# LedDriver7W.net
KiCad netlist of a schematic drawn in Altium Designer
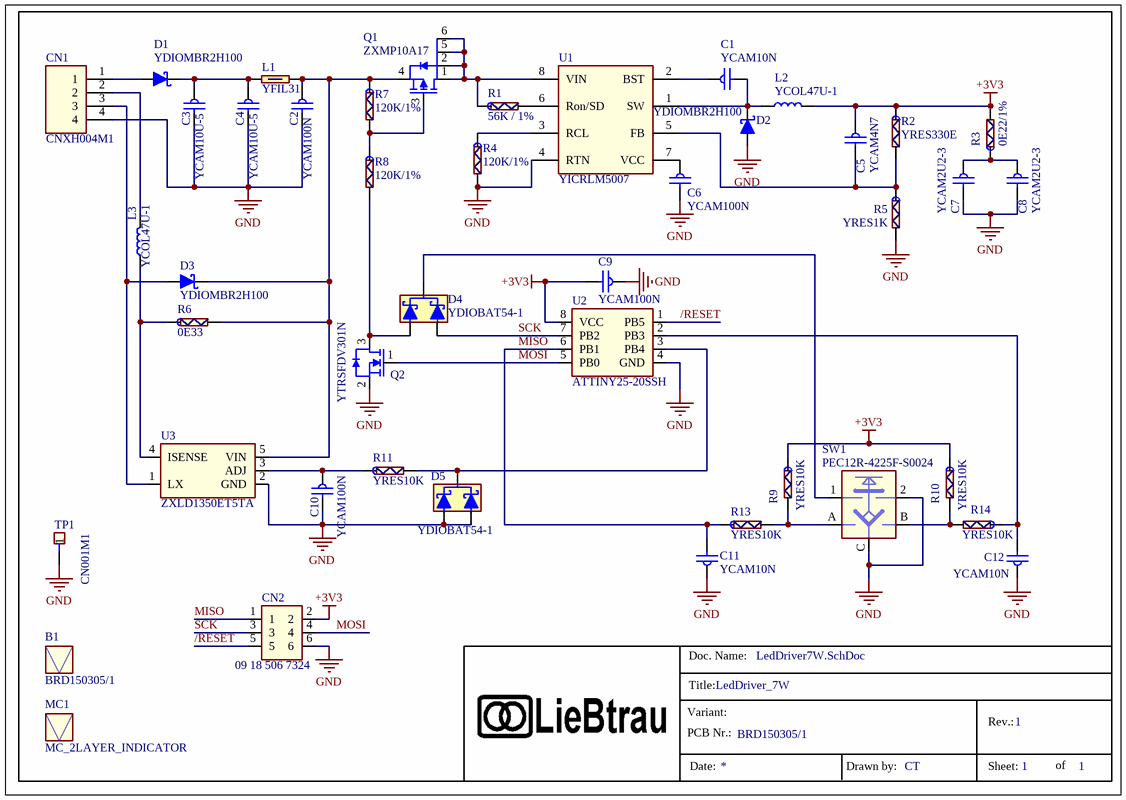
[diagram p0: LedDriver7W.SchDoc]

(export (version "E")
  (design (tool "Eeschema 10.0.6"))
  (components
    (comp (ref "B1") (value "~") (footprint "MC_BoardNr") (libsource (lib "Testing") (part "BD_PCB")))
    (comp (ref "C1")
      (value "YCAM10N")
      (footprint "CA_STD1206_H16")
      (description "10N")
      (libsource (lib "Testing") (part "CA_STD_NonPolar"))
    )
    (comp (ref "C2")
      (value "YCAM100N")
      (footprint "CA_STD1206_H16")
      (description "100N")
      (libsource (lib "Testing") (part "CA_STD_NonPolar"))
    )
    (comp (ref "C3")
      (value "YCAM10U-5")
      (footprint "CA_STD1206_H16")
      (description "10U")
      (libsource (lib "Testing") (part "CA_STD_NonPolar"))
    )
    (comp (ref "C4")
      (value "YCAM10U-5")
      (footprint "CA_STD1206_H16")
      (description "10U")
      (libsource (lib "Testing") (part "CA_STD_NonPolar"))
    )
    (comp (ref "C5")
      (value "YCAM4N7")
      (footprint "CA_STD1206_H16")
      (description "4N7")
      (libsource (lib "Testing") (part "CA_STD_NonPolar"))
    )
    (comp (ref "C6")
      (value "YCAM100N")
      (footprint "CA_STD1206_H16")
      (description "100N")
      (libsource (lib "Testing") (part "CA_STD_NonPolar"))
    )
    (comp (ref "C7")
      (value "YCAM2U2-3")
      (footprint "CA_STD1206_H16")
      (description "2U2")
      (libsource (lib "Testing") (part "CA_STD_NonPolar"))
    )
    (comp (ref "C8")
      (value "YCAM2U2-3")
      (footprint "CA_STD1206_H16")
      (description "2U2")
      (libsource (lib "Testing") (part "CA_STD_NonPolar"))
    )
    (comp (ref "C9")
      (value "YCAM100N")
      (footprint "CA_STD1206_H16")
      (description "100N")
      (libsource (lib "") (part "CA_STD_NonPolar_1"))
    )
    (comp (ref "C10")
      (value "YCAM100N")
      (footprint "CA_STD1206_H16")
      (description "100N")
      (libsource (lib "Testing") (part "CA_STD_NonPolar"))
    )
    (comp (ref "C11")
      (value "YCAM10N")
      (footprint "CA_STD1206_H16")
      (description "10N")
      (libsource (lib "Testing") (part "CA_STD_NonPolar"))
    )
    (comp (ref "C12")
      (value "YCAM10N")
      (footprint "CA_STD1206_H16")
      (description "10N")
      (libsource (lib "Testing") (part "CA_STD_NonPolar"))
    )
    (comp (ref "CN1")
      (value "CNXH004M1")
      (footprint "CN_JST-B4B-XH")
      (description "HEADER, VERT, 1x4WAY")
      (libsource (lib "Testing") (part "CN_4P"))
    )
    (comp (ref "CN2")
      (value "09 18 506 7324")
      (footprint "CN_HDR2x3_SHROUDED")
      (description "HEADER, VERT, N/LATCH, 2x3WAY")
      (libsource (lib "Testing") (part "CN_2x3P"))
    )
    (comp (ref "D1")
      (value "YDIOMBR2H100")
      (footprint "DI_SMB")
      (description "MBRS2H100")
      (libsource (lib "Testing") (part "DI_STD_Schottky"))
    )
    (comp (ref "D2")
      (value "YDIOMBR2H100")
      (footprint "DI_SMB")
      (description "MBRS2H100")
      (libsource (lib "Testing") (part "DI_STD_Schottky"))
    )
    (comp (ref "D3")
      (value "YDIOMBR2H100")
      (footprint "DI_SMB")
      (description "MBRS2H100")
      (libsource (lib "Testing") (part "DI_STD_Schottky"))
    )
    (comp (ref "D4")
      (value "YDIOBAT54-1")
      (footprint "SC_SOT23_3P")
      (description "BAT54C")
      (libsource (lib "Testing") (part "DI_BAT54C"))
    )
    (comp (ref "D5")
      (value "YDIOBAT54-1")
      (footprint "SC_SOT23_3P")
      (description "BAT54C")
      (libsource (lib "") (part "DI_BAT54C_1"))
    )
    (comp (ref "L1")
      (value "YFIL31")
      (footprint "CL_STD1206_H16")
      (description "600E")
      (libsource (lib "Testing") (part "CL_STD_FerriteBead"))
    )
    (comp (ref "L2")
      (value "YCOL47U-1")
      (footprint "CL_STD6045")
      (description "47UH")
      (libsource (lib "Testing") (part "CL_STD_Inductor"))
    )
    (comp (ref "L3")
      (value "YCOL47U-1")
      (footprint "CL_STD6045")
      (description "47UH")
      (libsource (lib "Testing") (part "CL_STD_Inductor"))
    )
    (comp (ref "MC1")
      (value "MC_2LAYER_INDICATOR")
      (footprint "MC_2LAYER_INDICATOR")
      (libsource (lib "Testing") (part "MC_MechPart_No_BOM"))
    )
    (comp (ref "Q1")
      (value "ZXMP10A17")
      (footprint "SC_SOT23_6P")
      (libsource (lib "Diverse") (part "TR_FETP_ZXMP10A17"))
    )
    (comp (ref "Q2")
      (value "YTRSFDV301N")
      (footprint "SC_SOT23_3P")
      (description "FDV301N")
      (libsource (lib "Testing") (part "TR_FETN_ENH-FDV301N"))
    )
    (comp (ref "R1")
      (value "56K / 1%")
      (footprint "RE_STD1206_H6")
      (description "56K")
      (libsource (lib "") (part "RE_STD_Resistor_3"))
    )
    (comp (ref "R2")
      (value "YRES330E")
      (footprint "RE_STD1206_H6")
      (description "330E")
      (libsource (lib "Testing") (part "RE_STD_Resistor"))
    )
    (comp (ref "R3")
      (value "0E22/1%")
      (footprint "RE_STD1206_H6")
      (description "0E22")
      (libsource (lib "") (part "RE_STD_Resistor_1"))
    )
    (comp (ref "R4")
      (value "120K/1%")
      (footprint "RE_STD1206_H6")
      (description "120K")
      (libsource (lib "Testing") (part "RE_STD_Resistor"))
    )
    (comp (ref "R5")
      (value "YRES1K")
      (footprint "RE_STD1206_H6")
      (description "1K")
      (libsource (lib "Testing") (part "RE_STD_Resistor"))
    )
    (comp (ref "R6")
      (value "0E33")
      (footprint "RE_STD1206_H6")
      (libsource (lib "") (part "RE_STD_Resistor_3"))
    )
    (comp (ref "R7")
      (value "120K/1%")
      (footprint "RE_STD1206_H6")
      (description "120K")
      (libsource (lib "Testing") (part "RE_STD_Resistor"))
    )
    (comp (ref "R8")
      (value "120K/1%")
      (footprint "RE_STD1206_H6")
      (description "120K")
      (libsource (lib "Testing") (part "RE_STD_Resistor"))
    )
    (comp (ref "R9")
      (value "YRES10K")
      (footprint "RE_STD1206_H6")
      (description "10K")
      (libsource (lib "Testing") (part "RE_STD_Resistor"))
    )
    (comp (ref "R10")
      (value "YRES10K")
      (footprint "RE_STD1206_H6")
      (description "10K")
      (libsource (lib "Testing") (part "RE_STD_Resistor"))
    )
    (comp (ref "R11")
      (value "YRES10K")
      (footprint "RE_STD1206_H6")
      (description "10K")
      (libsource (lib "") (part "RE_STD_Resistor_3"))
    )
    (comp (ref "R13")
      (value "YRES10K")
      (footprint "RE_STD1206_H6")
      (description "10K")
      (libsource (lib "") (part "RE_STD_Resistor_3"))
    )
    (comp (ref "R14")
      (value "YRES10K")
      (footprint "RE_STD1206_H6")
      (description "10K")
      (libsource (lib "") (part "RE_STD_Resistor_2"))
    )
    (comp (ref "SW1")
      (value "PEC12R-4225F-S0024")
      (footprint "SW_BOURNS_PEC12R")
      (description "rotary encoder 24 detents, switch")
      (libsource (lib "Diverse") (part "SW_BOURNS_PEC12R"))
    )
    (comp (ref "TP1")
      (value "CN001M1")
      (footprint "CN_TP_1MM")
      (description "TEST PIN")
      (libsource (lib "Testing") (part "CN_TESTPIN"))
    )
    (comp (ref "U1")
      (value "YICRLM5007")
      (footprint "SC_MSOP8")
      (description "LM5008AMM/NOPB")
      (libsource (lib "Testing") (part "IC_LM5009"))
    )
    (comp (ref "U2")
      (value "ATTINY25-20SSH")
      (footprint "SC_SO8_M")
      (libsource (lib "Diverse") (part "IC_ATTINY45"))
    )
    (comp (ref "U3")
      (value "ZXLD1350ET5TA")
      (footprint "SC_SOT23_5P")
      (description "LED driver")
      (libsource (lib "Diverse") (part "IC_ZXLD1350"))
    )
  )
  (nets
    (net (code "1") (name "+3V3") (class "Default")
      (node (ref "C5") (pin "1") (pinfunction "1_1") (pintype "passive"))
      (node (ref "C9") (pin "2") (pinfunction "2_2") (pintype "passive"))
      (node (ref "CN2") (pin "2") (pinfunction "2_2") (pintype "passive"))
      (node (ref "L2") (pin "2") (pinfunction "2_2") (pintype "passive"))
      (node (ref "R10") (pin "1") (pinfunction "1_1") (pintype "passive"))
      (node (ref "R2") (pin "1") (pinfunction "1_1") (pintype "passive"))
      (node (ref "R3") (pin "2") (pinfunction "2_2") (pintype "passive"))
      (node (ref "R9") (pin "1") (pinfunction "1_1") (pintype "passive"))
      (node (ref "U2") (pin "8") (pinfunction "VCC_8") (pintype "passive"))
    )
    (net (code "2") (name "/MISO") (class "Default")
      (node (ref "C11") (pin "2") (pinfunction "2_2") (pintype "passive"))
      (node (ref "CN2") (pin "1") (pinfunction "1_1") (pintype "passive"))
      (node (ref "R13") (pin "1") (pinfunction "1_1") (pintype "passive"))
      (node (ref "U2") (pin "6") (pinfunction "PB1_6") (pintype "passive"))
    )
    (net (code "3") (name "/MOSI") (class "Default")
      (node (ref "CN2") (pin "4") (pinfunction "4_4") (pintype "passive"))
      (node (ref "Q2") (pin "1") (pinfunction "G_1") (pintype "passive"))
      (node (ref "U2") (pin "5") (pinfunction "PB0_5") (pintype "passive"))
    )
    (net (code "4") (name "/SCK") (class "Default")
      (node (ref "CN2") (pin "3") (pinfunction "3_3") (pintype "passive"))
      (node (ref "D4") (pin "1") (pinfunction "A1_1") (pintype "passive"))
      (node (ref "U2") (pin "7") (pinfunction "PB2_7") (pintype "passive"))
    )
    (net (code "5") (name "/{slash}RESET") (class "Default")
      (node (ref "CN2") (pin "5") (pinfunction "5_5") (pintype "passive"))
      (node (ref "U2") (pin "1") (pinfunction "PB5_1") (pintype "passive"))
    )
    (net (code "6") (name "GND") (class "Default")
      (node (ref "C10") (pin "2") (pinfunction "2_2") (pintype "passive"))
      (node (ref "C11") (pin "1") (pinfunction "1_1") (pintype "passive"))
      (node (ref "C12") (pin "1") (pinfunction "1_1") (pintype "passive"))
      (node (ref "C2") (pin "2") (pinfunction "2_2") (pintype "passive"))
      (node (ref "C3") (pin "2") (pinfunction "2_2") (pintype "passive"))
      (node (ref "C4") (pin "2") (pinfunction "2_2") (pintype "passive"))
      (node (ref "C6") (pin "2") (pinfunction "2_2") (pintype "passive"))
      (node (ref "C7") (pin "2") (pinfunction "2_2") (pintype "passive"))
      (node (ref "C8") (pin "2") (pinfunction "2_2") (pintype "passive"))
      (node (ref "C9") (pin "1") (pinfunction "1_1") (pintype "passive"))
      (node (ref "CN1") (pin "4") (pinfunction "4_4") (pintype "passive"))
      (node (ref "CN2") (pin "6") (pinfunction "6_6") (pintype "passive"))
      (node (ref "D2") (pin "A") (pinfunction "A_A") (pintype "passive"))
      (node (ref "D5") (pin "1") (pinfunction "A1_1") (pintype "passive"))
      (node (ref "D5") (pin "2") (pinfunction "A2_2") (pintype "passive"))
      (node (ref "Q2") (pin "2") (pinfunction "S_2") (pintype "passive"))
      (node (ref "R4") (pin "2") (pinfunction "2_2") (pintype "passive"))
      (node (ref "R5") (pin "2") (pinfunction "2_2") (pintype "passive"))
      (node (ref "SW1") (pin "2") (pintype "passive"))
      (node (ref "SW1") (pin "C") (pintype "passive"))
      (node (ref "TP1") (pin "1") (pinfunction "1_1") (pintype "passive"))
      (node (ref "U1") (pin "4") (pinfunction "RTN_4") (pintype "power_in"))
      (node (ref "U2") (pin "4") (pinfunction "GND_4") (pintype "passive"))
      (node (ref "U3") (pin "2") (pinfunction "GND_2") (pintype "passive"))
    )
    (net (code "7") (name "Net-(C3-Pad1)") (class "Default")
      (node (ref "C3") (pin "1") (pinfunction "1_1") (pintype "passive"))
      (node (ref "C4") (pin "1") (pinfunction "1_1") (pintype "passive"))
      (node (ref "D1") (pin "C") (pinfunction "C_C") (pintype "passive"))
      (node (ref "L1") (pin "1") (pinfunction "1_1") (pintype "passive"))
    )
    (net (code "8") (name "Net-(C7-Pad1)") (class "Default")
      (node (ref "C7") (pin "1") (pinfunction "1_1") (pintype "passive"))
      (node (ref "C8") (pin "1") (pinfunction "1_1") (pintype "passive"))
      (node (ref "R3") (pin "1") (pinfunction "1_1") (pintype "passive"))
    )
    (net (code "9") (name "Net-(CN1-Pad1)") (class "Default")
      (node (ref "CN1") (pin "1") (pinfunction "1_1") (pintype "passive"))
      (node (ref "D1") (pin "A") (pinfunction "A_A") (pintype "passive"))
    )
    (net (code "10") (name "Net-(CN1-Pad2)") (class "Default")
      (node (ref "CN1") (pin "2") (pinfunction "2_2") (pintype "passive"))
      (node (ref "L3") (pin "2") (pinfunction "2_2") (pintype "passive"))
    )
    (net (code "11") (name "Net-(D4-A2)") (class "Default")
      (node (ref "D4") (pin "2") (pinfunction "A2_2") (pintype "passive"))
      (node (ref "Q2") (pin "3") (pinfunction "D_3") (pintype "passive"))
      (node (ref "R8") (pin "2") (pinfunction "2_2") (pintype "passive"))
    )
    (net (code "12") (name "Net-(D4-C)") (class "Default")
      (node (ref "D4") (pin "3") (pinfunction "C_3") (pintype "passive"))
      (node (ref "SW1") (pin "1") (pintype "passive"))
    )
    (net (code "13") (name "Net-(D5-C)") (class "Default")
      (node (ref "D5") (pin "3") (pinfunction "C_3") (pintype "passive"))
      (node (ref "R11") (pin "2") (pinfunction "2_2") (pintype "passive"))
      (node (ref "U2") (pin "3") (pinfunction "PB4_3") (pintype "passive"))
    )
    (net (code "14") (name "Net-(Q1-D)") (class "Default")
      (node (ref "Q1") (pin "3") (pinfunction "D_3") (pintype "passive"))
      (node (ref "R7") (pin "2") (pinfunction "2_2") (pintype "passive"))
      (node (ref "R8") (pin "1") (pinfunction "1_1") (pintype "passive"))
    )
    (net (code "15") (name "Net-(Q1-G)") (class "Default")
      (node (ref "Q1") (pin "1") (pinfunction "G_1") (pintype "passive"))
      (node (ref "Q1") (pin "2") (pinfunction "S_2") (pintype "passive"))
      (node (ref "Q1") (pin "5") (pinfunction "5_5") (pintype "passive"))
      (node (ref "Q1") (pin "6") (pinfunction "6_6") (pintype "passive"))
      (node (ref "R1") (pin "1") (pinfunction "1_1") (pintype "passive"))
      (node (ref "U1") (pin "8") (pinfunction "VIN_8") (pintype "power_in"))
    )
    (net (code "16") (name "Net-(R10-Pad2)") (class "Default")
      (node (ref "R10") (pin "2") (pinfunction "2_2") (pintype "passive"))
      (node (ref "R14") (pin "2") (pinfunction "2_2") (pintype "passive"))
      (node (ref "SW1") (pin "B") (pintype "passive"))
    )
    (net (code "17") (name "Net-(R13-Pad2)") (class "Default")
      (node (ref "R13") (pin "2") (pinfunction "2_2") (pintype "passive"))
      (node (ref "R9") (pin "2") (pinfunction "2_2") (pintype "passive"))
      (node (ref "SW1") (pin "A") (pintype "passive"))
    )
    (net (code "18") (name "Net-(U1-BST)") (class "Default")
      (node (ref "C1") (pin "1") (pinfunction "1_1") (pintype "passive"))
      (node (ref "U1") (pin "2") (pinfunction "BST_2") (pintype "passive"))
    )
    (net (code "19") (name "Net-(U1-FB)") (class "Default")
      (node (ref "C5") (pin "2") (pinfunction "2_2") (pintype "passive"))
      (node (ref "R2") (pin "2") (pinfunction "2_2") (pintype "passive"))
      (node (ref "R5") (pin "1") (pinfunction "1_1") (pintype "passive"))
      (node (ref "U1") (pin "5") (pinfunction "FB_5") (pintype "passive"))
    )
    (net (code "20") (name "Net-(U1-RCL)") (class "Default")
      (node (ref "R4") (pin "1") (pinfunction "1_1") (pintype "passive"))
      (node (ref "U1") (pin "3") (pinfunction "RCL_3") (pintype "passive"))
    )
    (net (code "21") (name "Net-(U1-Ron{slash}SD)") (class "Default")
      (node (ref "R1") (pin "2") (pinfunction "2_2") (pintype "passive"))
      (node (ref "U1") (pin "6") (pinfunction "Ron/SD_6") (pintype "passive"))
    )
    (net (code "22") (name "Net-(U1-SW)") (class "Default")
      (node (ref "C1") (pin "2") (pinfunction "2_2") (pintype "passive"))
      (node (ref "D2") (pin "C") (pinfunction "C_C") (pintype "passive"))
      (node (ref "L2") (pin "1") (pinfunction "1_1") (pintype "passive"))
      (node (ref "U1") (pin "1") (pinfunction "SW_1") (pintype "passive"))
    )
    (net (code "23") (name "Net-(U1-VCC)") (class "Default")
      (node (ref "C6") (pin "1") (pinfunction "1_1") (pintype "passive"))
      (node (ref "U1") (pin "7") (pinfunction "VCC_7") (pintype "passive"))
    )
    (net (code "24") (name "Net-(U2-PB3)") (class "Default")
      (node (ref "C12") (pin "2") (pinfunction "2_2") (pintype "passive"))
      (node (ref "R14") (pin "1") (pinfunction "1_1") (pintype "passive"))
      (node (ref "U2") (pin "2") (pinfunction "PB3_2") (pintype "passive"))
    )
    (net (code "25") (name "Net-(U3-ADJ)") (class "Default")
      (node (ref "C10") (pin "1") (pinfunction "1_1") (pintype "passive"))
      (node (ref "R11") (pin "1") (pinfunction "1_1") (pintype "passive"))
      (node (ref "U3") (pin "3") (pinfunction "ADJ_3") (pintype "passive"))
    )
    (net (code "26") (name "Net-(U3-ISENSE)") (class "Default")
      (node (ref "L3") (pin "1") (pinfunction "1_1") (pintype "passive"))
      (node (ref "R6") (pin "1") (pinfunction "1_1") (pintype "passive"))
      (node (ref "U3") (pin "4") (pinfunction "ISENSE_4") (pintype "passive"))
    )
    (net (code "27") (name "Net-(U3-LX)") (class "Default")
      (node (ref "CN1") (pin "3") (pinfunction "3_3") (pintype "passive"))
      (node (ref "D3") (pin "A") (pinfunction "A_A") (pintype "passive"))
      (node (ref "U3") (pin "1") (pinfunction "LX_1") (pintype "passive"))
    )
    (net (code "28") (name "Net-(U3-VIN)") (class "Default")
      (node (ref "C2") (pin "1") (pinfunction "1_1") (pintype "passive"))
      (node (ref "D3") (pin "C") (pinfunction "C_C") (pintype "passive"))
      (node (ref "L1") (pin "2") (pinfunction "2_2") (pintype "passive"))
      (node (ref "Q1") (pin "4") (pinfunction "4_4") (pintype "passive"))
      (node (ref "R6") (pin "2") (pinfunction "2_2") (pintype "passive"))
      (node (ref "R7") (pin "1") (pinfunction "1_1") (pintype "passive"))
      (node (ref "U3") (pin "5") (pinfunction "VIN_5") (pintype "passive"))
    )
  )
)
